# 05-Front_Panel_SFP_1.net
KiCad netlist of a schematic drawn in Altium Designer
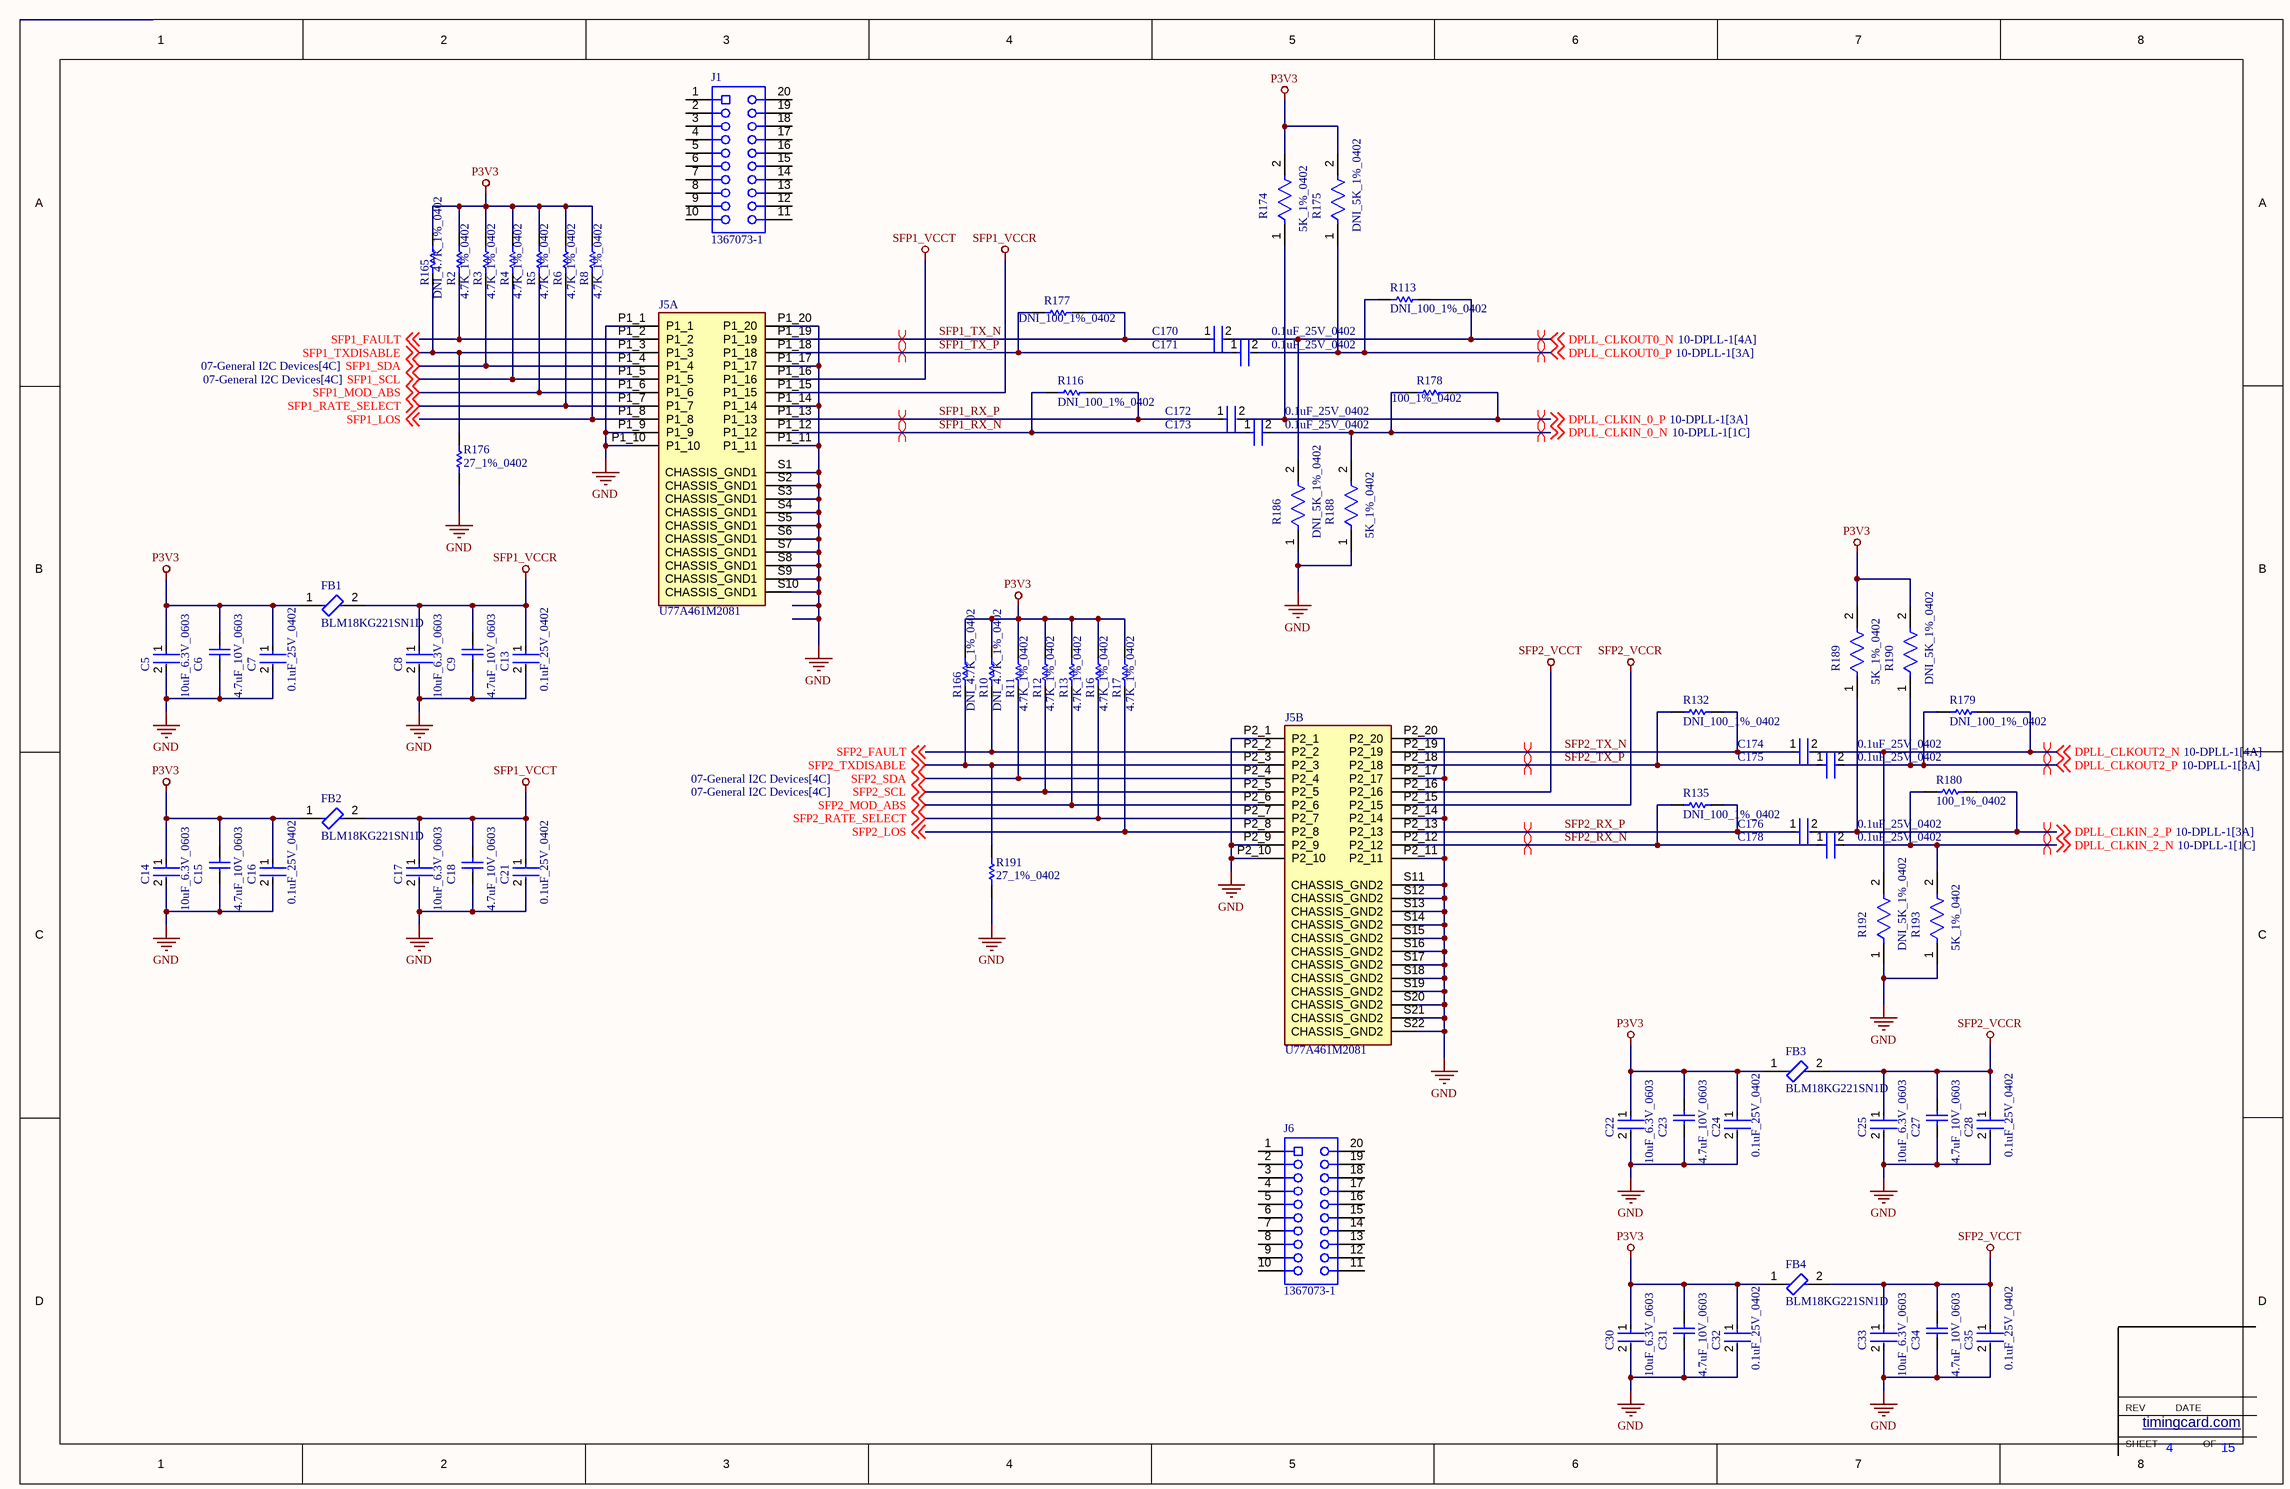
[diagram p0: 05-Front Panel SFP_1.SchDoc]

(export (version "E")
  (design (tool "Eeschema 10.0.6"))
  (components
    (comp (ref "C5")
      (value "10uF_6.3V_0603")
      (footprint "FP-C0603C106M9PACTU-MFG")
      (description "CAP CER 10UF 6.3V X5R 0603")
      (fields
        (field (name "MANUFACTURER PART NUMBER") "C0603C106M9PACTU")
        (field (name "MANUFACTURER") "Kemet")
      )
      (libsource (lib "Altium Content Vault") (part "b4654b650e69147ec39a6b967a45e02"))
    )
    (comp (ref "C6")
      (value "4.7uF_10V_0603")
      (footprint "CAPC1608X87X35NL15T15")
      (fields (field (name "PART NUMBER") "C0603C475K8PACTU") (field (name "MANUFACTURER") "Kemet"))
      (libsource (lib "Altium Content Vault") (part "CAP"))
    )
    (comp (ref "C7")
      (value "0.1uF_25V_0402")
      (footprint "FP-0402-L_1_0_1-W_0_5_0_1-IPC_C")
      (description "General Purpose Ceramic Capacitor, 0402, 100nF, 10%, X7R, 15%, 25V")
      (fields (field (name "VOLTAGE") "25V") (field (name "TOLERANCE") "10%"))
      (libsource (lib "Altium Content Vault") (part "b4654b650e69147ec39a6b967a45e02"))
    )
    (comp (ref "C8")
      (value "10uF_6.3V_0603")
      (footprint "FP-C0603C106M9PACTU-MFG")
      (description "CAP CER 10UF 6.3V X5R 0603")
      (fields
        (field (name "MANUFACTURER PART NUMBER") "C0603C106M9PACTU")
        (field (name "MANUFACTURER") "Kemet")
      )
      (libsource (lib "Altium Content Vault") (part "b4654b650e69147ec39a6b967a45e02"))
    )
    (comp (ref "C9")
      (value "4.7uF_10V_0603")
      (footprint "CAPC1608X87X35NL15T15")
      (fields (field (name "PART NUMBER") "C0603C475K8PACTU") (field (name "MANUFACTURER") "Kemet"))
      (libsource (lib "Altium Content Vault") (part "CAP"))
    )
    (comp (ref "C13")
      (value "0.1uF_25V_0402")
      (footprint "FP-0402-L_1_0_1-W_0_5_0_1-IPC_C")
      (description "General Purpose Ceramic Capacitor, 0402, 100nF, 10%, X7R, 15%, 25V")
      (fields (field (name "VOLTAGE") "25V") (field (name "TOLERANCE") "10%"))
      (libsource (lib "Altium Content Vault") (part "b4654b650e69147ec39a6b967a45e02"))
    )
    (comp (ref "C14")
      (value "10uF_6.3V_0603")
      (footprint "FP-C0603C106M9PACTU-MFG")
      (description "CAP CER 10UF 6.3V X5R 0603")
      (fields
        (field (name "MANUFACTURER PART NUMBER") "C0603C106M9PACTU")
        (field (name "MANUFACTURER") "Kemet")
      )
      (libsource (lib "Altium Content Vault") (part "b4654b650e69147ec39a6b967a45e02"))
    )
    (comp (ref "C15")
      (value "4.7uF_10V_0603")
      (footprint "CAPC1608X87X35NL15T15")
      (fields (field (name "PART NUMBER") "C0603C475K8PACTU") (field (name "MANUFACTURER") "Kemet"))
      (libsource (lib "Altium Content Vault") (part "CAP"))
    )
    (comp (ref "C16")
      (value "0.1uF_25V_0402")
      (footprint "FP-0402-L_1_0_1-W_0_5_0_1-IPC_C")
      (description "General Purpose Ceramic Capacitor, 0402, 100nF, 10%, X7R, 15%, 25V")
      (fields (field (name "VOLTAGE") "25V") (field (name "TOLERANCE") "10%"))
      (libsource (lib "Altium Content Vault") (part "b4654b650e69147ec39a6b967a45e02"))
    )
    (comp (ref "C17")
      (value "10uF_6.3V_0603")
      (footprint "FP-C0603C106M9PACTU-MFG")
      (description "CAP CER 10UF 6.3V X5R 0603")
      (fields
        (field (name "MANUFACTURER PART NUMBER") "C0603C106M9PACTU")
        (field (name "MANUFACTURER") "Kemet")
      )
      (libsource (lib "Altium Content Vault") (part "b4654b650e69147ec39a6b967a45e02"))
    )
    (comp (ref "C18")
      (value "4.7uF_10V_0603")
      (footprint "CAPC1608X87X35NL15T15")
      (fields (field (name "PART NUMBER") "C0603C475K8PACTU") (field (name "MANUFACTURER") "Kemet"))
      (libsource (lib "Altium Content Vault") (part "CAP"))
    )
    (comp (ref "C21")
      (value "0.1uF_25V_0402")
      (footprint "FP-0402-L_1_0_1-W_0_5_0_1-IPC_C")
      (description "General Purpose Ceramic Capacitor, 0402, 100nF, 10%, X7R, 15%, 25V")
      (fields (field (name "VOLTAGE") "25V") (field (name "TOLERANCE") "10%"))
      (libsource (lib "Altium Content Vault") (part "b4654b650e69147ec39a6b967a45e02"))
    )
    (comp (ref "C22")
      (value "10uF_6.3V_0603")
      (footprint "FP-C0603C106M9PACTU-MFG")
      (description "CAP CER 10UF 6.3V X5R 0603")
      (fields
        (field (name "MANUFACTURER PART NUMBER") "C0603C106M9PACTU")
        (field (name "MANUFACTURER") "Kemet")
      )
      (libsource (lib "Altium Content Vault") (part "b4654b650e69147ec39a6b967a45e02"))
    )
    (comp (ref "C23")
      (value "4.7uF_10V_0603")
      (footprint "CAPC1608X87X35NL15T15")
      (fields (field (name "PART NUMBER") "C0603C475K8PACTU") (field (name "MANUFACTURER") "Kemet"))
      (libsource (lib "Altium Content Vault") (part "CAP"))
    )
    (comp (ref "C24")
      (value "0.1uF_25V_0402")
      (footprint "FP-0402-L_1_0_1-W_0_5_0_1-IPC_C")
      (description "General Purpose Ceramic Capacitor, 0402, 100nF, 10%, X7R, 15%, 25V")
      (fields (field (name "VOLTAGE") "25V") (field (name "TOLERANCE") "10%"))
      (libsource (lib "Altium Content Vault") (part "b4654b650e69147ec39a6b967a45e02"))
    )
    (comp (ref "C25")
      (value "10uF_6.3V_0603")
      (footprint "FP-C0603C106M9PACTU-MFG")
      (description "CAP CER 10UF 6.3V X5R 0603")
      (fields
        (field (name "MANUFACTURER PART NUMBER") "C0603C106M9PACTU")
        (field (name "MANUFACTURER") "Kemet")
      )
      (libsource (lib "Altium Content Vault") (part "b4654b650e69147ec39a6b967a45e02"))
    )
    (comp (ref "C27")
      (value "4.7uF_10V_0603")
      (footprint "CAPC1608X87X35NL15T15")
      (fields (field (name "PART NUMBER") "C0603C475K8PACTU") (field (name "MANUFACTURER") "Kemet"))
      (libsource (lib "Altium Content Vault") (part "CAP"))
    )
    (comp (ref "C28")
      (value "0.1uF_25V_0402")
      (footprint "FP-0402-L_1_0_1-W_0_5_0_1-IPC_C")
      (description "General Purpose Ceramic Capacitor, 0402, 100nF, 10%, X7R, 15%, 25V")
      (fields (field (name "VOLTAGE") "25V") (field (name "TOLERANCE") "10%"))
      (libsource (lib "Altium Content Vault") (part "b4654b650e69147ec39a6b967a45e02"))
    )
    (comp (ref "C30")
      (value "10uF_6.3V_0603")
      (footprint "FP-C0603C106M9PACTU-MFG")
      (description "CAP CER 10UF 6.3V X5R 0603")
      (fields
        (field (name "MANUFACTURER PART NUMBER") "C0603C106M9PACTU")
        (field (name "MANUFACTURER") "Kemet")
      )
      (libsource (lib "Altium Content Vault") (part "b4654b650e69147ec39a6b967a45e02"))
    )
    (comp (ref "C31")
      (value "4.7uF_10V_0603")
      (footprint "CAPC1608X87X35NL15T15")
      (fields (field (name "PART NUMBER") "C0603C475K8PACTU") (field (name "MANUFACTURER") "Kemet"))
      (libsource (lib "Altium Content Vault") (part "CAP"))
    )
    (comp (ref "C32")
      (value "0.1uF_25V_0402")
      (footprint "FP-0402-L_1_0_1-W_0_5_0_1-IPC_C")
      (description "General Purpose Ceramic Capacitor, 0402, 100nF, 10%, X7R, 15%, 25V")
      (fields (field (name "VOLTAGE") "25V") (field (name "TOLERANCE") "10%"))
      (libsource (lib "Altium Content Vault") (part "b4654b650e69147ec39a6b967a45e02"))
    )
    (comp (ref "C33")
      (value "10uF_6.3V_0603")
      (footprint "FP-C0603C106M9PACTU-MFG")
      (description "CAP CER 10UF 6.3V X5R 0603")
      (fields
        (field (name "MANUFACTURER PART NUMBER") "C0603C106M9PACTU")
        (field (name "MANUFACTURER") "Kemet")
      )
      (libsource (lib "Altium Content Vault") (part "b4654b650e69147ec39a6b967a45e02"))
    )
    (comp (ref "C34")
      (value "4.7uF_10V_0603")
      (footprint "CAPC1608X87X35NL15T15")
      (fields (field (name "PART NUMBER") "C0603C475K8PACTU") (field (name "MANUFACTURER") "Kemet"))
      (libsource (lib "Altium Content Vault") (part "CAP"))
    )
    (comp (ref "C35")
      (value "0.1uF_25V_0402")
      (footprint "FP-0402-L_1_0_1-W_0_5_0_1-IPC_C")
      (description "General Purpose Ceramic Capacitor, 0402, 100nF, 10%, X7R, 15%, 25V")
      (fields (field (name "VOLTAGE") "25V") (field (name "TOLERANCE") "10%"))
      (libsource (lib "Altium Content Vault") (part "b4654b650e69147ec39a6b967a45e02"))
    )
    (comp (ref "C170")
      (value "0.1uF_25V_0402")
      (footprint "FP-0402-L_1_0_1-W_0_5_0_1-IPC_C")
      (description "General Purpose Ceramic Capacitor, 0402, 100nF, 10%, X7R, 15%, 25V")
      (fields (field (name "VOLTAGE") "25V") (field (name "TOLERANCE") "10%"))
      (libsource (lib "Altium Content Vault") (part "b4654b650e69147ec39a6b967a45e02"))
    )
    (comp (ref "C171")
      (value "0.1uF_25V_0402")
      (footprint "FP-0402-L_1_0_1-W_0_5_0_1-IPC_C")
      (description "General Purpose Ceramic Capacitor, 0402, 100nF, 10%, X7R, 15%, 25V")
      (fields (field (name "VOLTAGE") "25V") (field (name "TOLERANCE") "10%"))
      (libsource (lib "Altium Content Vault") (part "b4654b650e69147ec39a6b967a45e02"))
    )
    (comp (ref "C172")
      (value "0.1uF_25V_0402")
      (footprint "FP-0402-L_1_0_1-W_0_5_0_1-IPC_C")
      (description "General Purpose Ceramic Capacitor, 0402, 100nF, 10%, X7R, 15%, 25V")
      (fields (field (name "VOLTAGE") "25V") (field (name "TOLERANCE") "10%"))
      (libsource (lib "Altium Content Vault") (part "b4654b650e69147ec39a6b967a45e02"))
    )
    (comp (ref "C173")
      (value "0.1uF_25V_0402")
      (footprint "FP-0402-L_1_0_1-W_0_5_0_1-IPC_C")
      (description "General Purpose Ceramic Capacitor, 0402, 100nF, 10%, X7R, 15%, 25V")
      (fields (field (name "VOLTAGE") "25V") (field (name "TOLERANCE") "10%"))
      (libsource (lib "Altium Content Vault") (part "b4654b650e69147ec39a6b967a45e02"))
    )
    (comp (ref "C174")
      (value "0.1uF_25V_0402")
      (footprint "FP-0402-L_1_0_1-W_0_5_0_1-IPC_C")
      (description "General Purpose Ceramic Capacitor, 0402, 100nF, 10%, X7R, 15%, 25V")
      (fields (field (name "VOLTAGE") "25V") (field (name "TOLERANCE") "10%"))
      (libsource (lib "Altium Content Vault") (part "b4654b650e69147ec39a6b967a45e02"))
    )
    (comp (ref "C175")
      (value "0.1uF_25V_0402")
      (footprint "FP-0402-L_1_0_1-W_0_5_0_1-IPC_C")
      (description "General Purpose Ceramic Capacitor, 0402, 100nF, 10%, X7R, 15%, 25V")
      (fields (field (name "VOLTAGE") "25V") (field (name "TOLERANCE") "10%"))
      (libsource (lib "Altium Content Vault") (part "b4654b650e69147ec39a6b967a45e02"))
    )
    (comp (ref "C176")
      (value "0.1uF_25V_0402")
      (footprint "FP-0402-L_1_0_1-W_0_5_0_1-IPC_C")
      (description "General Purpose Ceramic Capacitor, 0402, 100nF, 10%, X7R, 15%, 25V")
      (fields (field (name "VOLTAGE") "25V") (field (name "TOLERANCE") "10%"))
      (libsource (lib "Altium Content Vault") (part "b4654b650e69147ec39a6b967a45e02"))
    )
    (comp (ref "C178")
      (value "0.1uF_25V_0402")
      (footprint "FP-0402-L_1_0_1-W_0_5_0_1-IPC_C")
      (description "General Purpose Ceramic Capacitor, 0402, 100nF, 10%, X7R, 15%, 25V")
      (fields (field (name "VOLTAGE") "25V") (field (name "TOLERANCE") "10%"))
      (libsource (lib "Altium Content Vault") (part "b4654b650e69147ec39a6b967a45e02"))
    )
    (comp (ref "FB1")
      (value "BLM18KG221SN1D")
      (footprint "FP-BLM18-0_15-t0_8-IPC_B")
      (description "Chip Ferrite Bead, 0603, 220Ω @ 100MHz, 0.05Ω, 25%, 2.2A")
      (fields (field (name "TOLERANCE") "25%"))
      (libsource (lib "Altium Content Vault") (part "5f30dd21d616792df468990f7003faa"))
    )
    (comp (ref "FB2")
      (value "BLM18KG221SN1D")
      (footprint "FP-BLM18-0_15-t0_8-IPC_B")
      (description "Chip Ferrite Bead, 0603, 220Ω @ 100MHz, 0.05Ω, 25%, 2.2A")
      (fields (field (name "TOLERANCE") "25%"))
      (libsource (lib "Altium Content Vault") (part "5f30dd21d616792df468990f7003faa"))
    )
    (comp (ref "FB3")
      (value "BLM18KG221SN1D")
      (footprint "FP-BLM18-0_15-t0_8-IPC_B")
      (description "Chip Ferrite Bead, 0603, 220Ω @ 100MHz, 0.05Ω, 25%, 2.2A")
      (fields (field (name "TOLERANCE") "25%"))
      (libsource (lib "Altium Content Vault") (part "5f30dd21d616792df468990f7003faa"))
    )
    (comp (ref "FB4")
      (value "BLM18KG221SN1D")
      (footprint "FP-BLM18-0_15-t0_8-IPC_B")
      (description "Chip Ferrite Bead, 0603, 220Ω @ 100MHz, 0.05Ω, 25%, 2.2A")
      (fields (field (name "TOLERANCE") "25%"))
      (libsource (lib "Altium Content Vault") (part "5f30dd21d616792df468990f7003faa"))
    )
    (comp (ref "J1")
      (value "1367073-1")
      (footprint "TECO-1367073-1_V")
      (fields (field (name "MANUFACTURER") "TE Connectivity"))
      (libsource (lib "Altium Content Vault") (part "CN-2P-F-R20_B"))
    )
    (comp (ref "J5")
      (value "U77A461M2081")
      (footprint "AMPHENOL_U77A461M2081")
      (fields (field (name "MF") "AMPHENOL ICC / FCI"))
      (libsource (lib "U77A461M2081") (part "U77A461M2081"))
    )
    (comp (ref "J6")
      (value "1367073-1")
      (footprint "TECO-1367073-1_V")
      (fields (field (name "MANUFACTURER") "TE Connectivity"))
      (libsource (lib "Altium Content Vault") (part "CN-2P-F-R20_B"))
    )
    (comp (ref "R2")
      (value "4.7K_1%_0402")
      (footprint "RESC1005X40X25NL10T10")
      (fields (field (name "MANUFACTURER") "Bourns") (field (name "PART NUMBER") "CR0402-FX-4701GLF"))
      (libsource (lib "Altium Content Vault") (part "RES"))
    )
    (comp (ref "R3")
      (value "4.7K_1%_0402")
      (footprint "RESC1005X40X25NL10T10")
      (fields (field (name "MANUFACTURER") "Bourns") (field (name "PART NUMBER") "CR0402-FX-4701GLF"))
      (libsource (lib "Altium Content Vault") (part "RES"))
    )
    (comp (ref "R4")
      (value "4.7K_1%_0402")
      (footprint "RESC1005X40X25NL10T10")
      (fields (field (name "MANUFACTURER") "Bourns") (field (name "PART NUMBER") "CR0402-FX-4701GLF"))
      (libsource (lib "Altium Content Vault") (part "RES"))
    )
    (comp (ref "R5")
      (value "4.7K_1%_0402")
      (footprint "RESC1005X40X25NL10T10")
      (fields (field (name "MANUFACTURER") "Bourns") (field (name "PART NUMBER") "CR0402-FX-4701GLF"))
      (libsource (lib "Altium Content Vault") (part "RES"))
    )
    (comp (ref "R6")
      (value "4.7K_1%_0402")
      (footprint "RESC1005X40X25NL10T10")
      (fields (field (name "MANUFACTURER") "Bourns") (field (name "PART NUMBER") "CR0402-FX-4701GLF"))
      (libsource (lib "Altium Content Vault") (part "RES"))
    )
    (comp (ref "R8")
      (value "4.7K_1%_0402")
      (footprint "RESC1005X40X25NL10T10")
      (fields (field (name "MANUFACTURER") "Bourns") (field (name "PART NUMBER") "CR0402-FX-4701GLF"))
      (libsource (lib "Altium Content Vault") (part "RES"))
    )
    (comp (ref "R10")
      (value "DNI_4.7K_1%_0402")
      (footprint "RESC1005X40X25NL10T10")
      (fields (field (name "MANUFACTURER") "Bourns") (field (name "PART NUMBER") "CR0402-FX-4701GLF"))
      (libsource (lib "Altium Content Vault") (part "RES"))
    )
    (comp (ref "R11")
      (value "4.7K_1%_0402")
      (footprint "RESC1005X40X25NL10T10")
      (fields (field (name "MANUFACTURER") "Bourns") (field (name "PART NUMBER") "CR0402-FX-4701GLF"))
      (libsource (lib "Altium Content Vault") (part "RES"))
    )
    (comp (ref "R12")
      (value "4.7K_1%_0402")
      (footprint "RESC1005X40X25NL10T10")
      (fields (field (name "MANUFACTURER") "Bourns") (field (name "PART NUMBER") "CR0402-FX-4701GLF"))
      (libsource (lib "Altium Content Vault") (part "RES"))
    )
    (comp (ref "R13")
      (value "4.7K_1%_0402")
      (footprint "RESC1005X40X25NL10T10")
      (fields (field (name "MANUFACTURER") "Bourns") (field (name "PART NUMBER") "CR0402-FX-4701GLF"))
      (libsource (lib "Altium Content Vault") (part "RES"))
    )
    (comp (ref "R16")
      (value "4.7K_1%_0402")
      (footprint "RESC1005X40X25NL10T10")
      (fields (field (name "MANUFACTURER") "Bourns") (field (name "PART NUMBER") "CR0402-FX-4701GLF"))
      (libsource (lib "Altium Content Vault") (part "RES"))
    )
    (comp (ref "R17")
      (value "4.7K_1%_0402")
      (footprint "RESC1005X40X25NL10T10")
      (fields (field (name "MANUFACTURER") "Bourns") (field (name "PART NUMBER") "CR0402-FX-4701GLF"))
      (libsource (lib "Altium Content Vault") (part "RES"))
    )
    (comp (ref "R113")
      (value "DNI_100_1%_0402")
      (footprint "RESC1005X40X25NL05T10")
      (fields (field (name "MANUFACTURER") "Yageo") (field (name "PART NUMBER") "RC0402FR-13100RL"))
      (libsource (lib "Altium Content Vault") (part "RES"))
    )
    (comp (ref "R116")
      (value "DNI_100_1%_0402")
      (footprint "RESC1005X40X25NL05T10")
      (fields (field (name "MANUFACTURER") "Yageo") (field (name "PART NUMBER") "RC0402FR-13100RL"))
      (libsource (lib "Altium Content Vault") (part "RES"))
    )
    (comp (ref "R132")
      (value "DNI_100_1%_0402")
      (footprint "RESC1005X40X25NL05T10")
      (fields (field (name "MANUFACTURER") "Yageo") (field (name "PART NUMBER") "RC0402FR-13100RL"))
      (libsource (lib "Altium Content Vault") (part "RES"))
    )
    (comp (ref "R135")
      (value "DNI_100_1%_0402")
      (footprint "RESC1005X40X25NL05T10")
      (fields (field (name "MANUFACTURER") "Yageo") (field (name "PART NUMBER") "RC0402FR-13100RL"))
      (libsource (lib "Altium Content Vault") (part "RES"))
    )
    (comp (ref "R165")
      (value "DNI_4.7K_1%_0402")
      (footprint "RESC1005X40X25NL10T10")
      (fields (field (name "MANUFACTURER") "Bourns") (field (name "PART NUMBER") "CR0402-FX-4701GLF"))
      (libsource (lib "Altium Content Vault") (part "RES"))
    )
    (comp (ref "R166")
      (value "DNI_4.7K_1%_0402")
      (footprint "RESC1005X40X25NL10T10")
      (fields (field (name "MANUFACTURER") "Bourns") (field (name "PART NUMBER") "CR0402-FX-4701GLF"))
      (libsource (lib "Altium Content Vault") (part "RES"))
    )
    (comp (ref "R174")
      (value "5K_1%_0402")
      (footprint "FP-RC0402-MFG")
      (description "RES SMD 5K OHM 1% 1/16W 0402")
      (fields (field (name "MANUFACTURER") "Yageo") (field (name "TOLERANCE") "1%"))
      (libsource (lib "Altium Content Vault") (part "1029c3af85768c4190bb7ad29bc67b5"))
    )
    (comp (ref "R175")
      (value "DNI_5K_1%_0402")
      (footprint "FP-RC0402-MFG")
      (description "RES SMD 5K OHM 1% 1/16W 0402")
      (fields (field (name "MANUFACTURER") "Yageo") (field (name "TOLERANCE") "1%"))
      (libsource (lib "Altium Content Vault") (part "1029c3af85768c4190bb7ad29bc67b5"))
    )
    (comp (ref "R176")
      (value "27_1%_0402")
      (footprint "RESC1005X40X25NL05T05")
      (fields (field (name "PART NUMBER") "CRCW040227R0FKED") (field (name "MANUFACTURER") "Vishay Dale"))
      (libsource (lib "Altium Content Vault") (part "RES"))
    )
    (comp (ref "R177")
      (value "DNI_100_1%_0402")
      (footprint "RESC1005X40X25NL05T10")
      (fields (field (name "MANUFACTURER") "Yageo") (field (name "PART NUMBER") "RC0402FR-13100RL"))
      (libsource (lib "Altium Content Vault") (part "RES"))
    )
    (comp (ref "R178")
      (value "100_1%_0402")
      (footprint "RESC1005X40X25NL05T10")
      (fields (field (name "MANUFACTURER") "Yageo") (field (name "PART NUMBER") "RC0402FR-13100RL"))
      (libsource (lib "Altium Content Vault") (part "RES"))
    )
    (comp (ref "R179")
      (value "DNI_100_1%_0402")
      (footprint "RESC1005X40X25NL05T10")
      (fields (field (name "MANUFACTURER") "Yageo") (field (name "PART NUMBER") "RC0402FR-13100RL"))
      (libsource (lib "Altium Content Vault") (part "RES"))
    )
    (comp (ref "R180")
      (value "100_1%_0402")
      (footprint "RESC1005X40X25NL05T10")
      (fields (field (name "MANUFACTURER") "Yageo") (field (name "PART NUMBER") "RC0402FR-13100RL"))
      (libsource (lib "Altium Content Vault") (part "RES"))
    )
    (comp (ref "R186")
      (value "DNI_5K_1%_0402")
      (footprint "FP-RC0402-MFG")
      (description "RES SMD 5K OHM 1% 1/16W 0402")
      (fields (field (name "MANUFACTURER") "Yageo") (field (name "TOLERANCE") "1%"))
      (libsource (lib "Altium Content Vault") (part "1029c3af85768c4190bb7ad29bc67b5"))
    )
    (comp (ref "R188")
      (value "5K_1%_0402")
      (footprint "FP-RC0402-MFG")
      (description "RES SMD 5K OHM 1% 1/16W 0402")
      (fields (field (name "MANUFACTURER") "Yageo") (field (name "TOLERANCE") "1%"))
      (libsource (lib "Altium Content Vault") (part "1029c3af85768c4190bb7ad29bc67b5"))
    )
    (comp (ref "R189")
      (value "5K_1%_0402")
      (footprint "FP-RC0402-MFG")
      (description "RES SMD 5K OHM 1% 1/16W 0402")
      (fields (field (name "MANUFACTURER") "Yageo") (field (name "TOLERANCE") "1%"))
      (libsource (lib "Altium Content Vault") (part "1029c3af85768c4190bb7ad29bc67b5"))
    )
    (comp (ref "R190")
      (value "DNI_5K_1%_0402")
      (footprint "FP-RC0402-MFG")
      (description "RES SMD 5K OHM 1% 1/16W 0402")
      (fields (field (name "MANUFACTURER") "Yageo") (field (name "TOLERANCE") "1%"))
      (libsource (lib "Altium Content Vault") (part "1029c3af85768c4190bb7ad29bc67b5"))
    )
    (comp (ref "R191")
      (value "27_1%_0402")
      (footprint "RESC1005X40X25NL05T05")
      (fields (field (name "PART NUMBER") "CRCW040227R0FKED") (field (name "MANUFACTURER") "Vishay Dale"))
      (libsource (lib "Altium Content Vault") (part "RES"))
    )
    (comp (ref "R192")
      (value "DNI_5K_1%_0402")
      (footprint "FP-RC0402-MFG")
      (description "RES SMD 5K OHM 1% 1/16W 0402")
      (fields (field (name "MANUFACTURER") "Yageo") (field (name "TOLERANCE") "1%"))
      (libsource (lib "Altium Content Vault") (part "1029c3af85768c4190bb7ad29bc67b5"))
    )
    (comp (ref "R193")
      (value "5K_1%_0402")
      (footprint "FP-RC0402-MFG")
      (description "RES SMD 5K OHM 1% 1/16W 0402")
      (fields (field (name "MANUFACTURER") "Yageo") (field (name "TOLERANCE") "1%"))
      (libsource (lib "Altium Content Vault") (part "1029c3af85768c4190bb7ad29bc67b5"))
    )
  )
  (nets
    (net (code "1") (name "/SFP1_RX_N") (class "Default")
      (node (ref "C173") (pin "1") (pinfunction "1_1") (pintype "passive"))
      (node (ref "J5") (pin "P1_12") (pinfunction "P1_12_P1_12") (pintype "passive"))
      (node (ref "R116") (pin "1") (pinfunction "1_1") (pintype "passive"))
    )
    (net (code "2") (name "/SFP1_RX_P") (class "Default")
      (node (ref "C172") (pin "1") (pinfunction "1_1") (pintype "passive"))
      (node (ref "J5") (pin "P1_13") (pinfunction "P1_13_P1_13") (pintype "passive"))
      (node (ref "R116") (pin "2") (pinfunction "2_2") (pintype "passive"))
    )
    (net (code "3") (name "/SFP1_TX_N") (class "Default")
      (node (ref "C170") (pin "1") (pinfunction "1_1") (pintype "passive"))
      (node (ref "J5") (pin "P1_19") (pinfunction "P1_19_P1_19") (pintype "passive"))
      (node (ref "R177") (pin "2") (pinfunction "2_2") (pintype "passive"))
    )
    (net (code "4") (name "/SFP1_TX_P") (class "Default")
      (node (ref "C171") (pin "1") (pinfunction "1_1") (pintype "passive"))
      (node (ref "J5") (pin "P1_18") (pinfunction "P1_18_P1_18") (pintype "passive"))
      (node (ref "R177") (pin "1") (pinfunction "1_1") (pintype "passive"))
    )
    (net (code "5") (name "/SFP2_RX_N") (class "Default")
      (node (ref "C178") (pin "1") (pinfunction "1_1") (pintype "passive"))
      (node (ref "J5") (pin "P2_12") (pinfunction "P2_12_P2_12") (pintype "passive"))
      (node (ref "R135") (pin "1") (pinfunction "1_1") (pintype "passive"))
    )
    (net (code "6") (name "/SFP2_RX_P") (class "Default")
      (node (ref "C176") (pin "1") (pinfunction "1_1") (pintype "passive"))
      (node (ref "J5") (pin "P2_13") (pinfunction "P2_13_P2_13") (pintype "passive"))
      (node (ref "R135") (pin "2") (pinfunction "2_2") (pintype "passive"))
    )
    (net (code "7") (name "/SFP2_TX_N") (class "Default")
      (node (ref "C174") (pin "1") (pinfunction "1_1") (pintype "passive"))
      (node (ref "J5") (pin "P2_19") (pinfunction "P2_19_P2_19") (pintype "passive"))
      (node (ref "R132") (pin "2") (pinfunction "2_2") (pintype "passive"))
    )
    (net (code "8") (name "/SFP2_TX_P") (class "Default")
      (node (ref "C175") (pin "1") (pinfunction "1_1") (pintype "passive"))
      (node (ref "J5") (pin "P2_18") (pinfunction "P2_18_P2_18") (pintype "passive"))
      (node (ref "R132") (pin "1") (pinfunction "1_1") (pintype "passive"))
    )
    (net (code "9") (name "DPLL_CLKIN_0_N") (class "Default")
      (node (ref "C173") (pin "2") (pinfunction "2_2") (pintype "passive"))
      (node (ref "R178") (pin "1") (pinfunction "1_1") (pintype "passive"))
      (node (ref "R188") (pin "2") (pinfunction "2_2") (pintype "passive"))
    )
    (net (code "10") (name "DPLL_CLKIN_0_P") (class "Default")
      (node (ref "C172") (pin "2") (pinfunction "2_2") (pintype "passive"))
      (node (ref "R174") (pin "1") (pinfunction "1_1") (pintype "passive"))
      (node (ref "R178") (pin "2") (pinfunction "2_2") (pintype "passive"))
    )
    (net (code "11") (name "DPLL_CLKIN_2_N") (class "Default")
      (node (ref "C178") (pin "2") (pinfunction "2_2") (pintype "passive"))
      (node (ref "R180") (pin "1") (pinfunction "1_1") (pintype "passive"))
      (node (ref "R193") (pin "2") (pinfunction "2_2") (pintype "passive"))
    )
    (net (code "12") (name "DPLL_CLKIN_2_P") (class "Default")
      (node (ref "C176") (pin "2") (pinfunction "2_2") (pintype "passive"))
      (node (ref "R180") (pin "2") (pinfunction "2_2") (pintype "passive"))
      (node (ref "R189") (pin "1") (pinfunction "1_1") (pintype "passive"))
    )
    (net (code "13") (name "DPLL_CLKOUT0_N") (class "Default")
      (node (ref "C170") (pin "2") (pinfunction "2_2") (pintype "passive"))
      (node (ref "R113") (pin "2") (pinfunction "2_2") (pintype "passive"))
      (node (ref "R186") (pin "2") (pinfunction "2_2") (pintype "passive"))
    )
    (net (code "14") (name "DPLL_CLKOUT0_P") (class "Default")
      (node (ref "C171") (pin "2") (pinfunction "2_2") (pintype "passive"))
      (node (ref "R113") (pin "1") (pinfunction "1_1") (pintype "passive"))
      (node (ref "R175") (pin "1") (pinfunction "1_1") (pintype "passive"))
    )
    (net (code "15") (name "DPLL_CLKOUT2_N") (class "Default")
      (node (ref "C174") (pin "2") (pinfunction "2_2") (pintype "passive"))
      (node (ref "R179") (pin "2") (pinfunction "2_2") (pintype "passive"))
      (node (ref "R192") (pin "2") (pinfunction "2_2") (pintype "passive"))
    )
    (net (code "16") (name "DPLL_CLKOUT2_P") (class "Default")
      (node (ref "C175") (pin "2") (pinfunction "2_2") (pintype "passive"))
      (node (ref "R179") (pin "1") (pinfunction "1_1") (pintype "passive"))
      (node (ref "R190") (pin "1") (pinfunction "1_1") (pintype "passive"))
    )
    (net (code "17") (name "GND") (class "Default")
      (node (ref "C13") (pin "2") (pinfunction "2_2") (pintype "passive"))
      (node (ref "C14") (pin "2") (pinfunction "2_2") (pintype "passive"))
      (node (ref "C15") (pin "1") (pinfunction "1_1") (pintype "passive"))
      (node (ref "C16") (pin "2") (pinfunction "2_2") (pintype "passive"))
      (node (ref "C17") (pin "2") (pinfunction "2_2") (pintype "passive"))
      (node (ref "C18") (pin "1") (pinfunction "1_1") (pintype "passive"))
      (node (ref "C21") (pin "2") (pinfunction "2_2") (pintype "passive"))
      (node (ref "C22") (pin "2") (pinfunction "2_2") (pintype "passive"))
      (node (ref "C23") (pin "1") (pinfunction "1_1") (pintype "passive"))
      (node (ref "C24") (pin "2") (pinfunction "2_2") (pintype "passive"))
      (node (ref "C25") (pin "2") (pinfunction "2_2") (pintype "passive"))
      (node (ref "C27") (pin "1") (pinfunction "1_1") (pintype "passive"))
      (node (ref "C28") (pin "2") (pinfunction "2_2") (pintype "passive"))
      (node (ref "C30") (pin "2") (pinfunction "2_2") (pintype "passive"))
      (node (ref "C31") (pin "1") (pinfunction "1_1") (pintype "passive"))
      (node (ref "C32") (pin "2") (pinfunction "2_2") (pintype "passive"))
      (node (ref "C33") (pin "2") (pinfunction "2_2") (pintype "passive"))
      (node (ref "C34") (pin "1") (pinfunction "1_1") (pintype "passive"))
      (node (ref "C35") (pin "2") (pinfunction "2_2") (pintype "passive"))
      (node (ref "C5") (pin "2") (pinfunction "2_2") (pintype "passive"))
      (node (ref "C6") (pin "1") (pinfunction "1_1") (pintype "passive"))
      (node (ref "C7") (pin "2") (pinfunction "2_2") (pintype "passive"))
      (node (ref "C8") (pin "2") (pinfunction "2_2") (pintype "passive"))
      (node (ref "C9") (pin "1") (pinfunction "1_1") (pintype "passive"))
      (node (ref "J5") (pin "P1_1") (pinfunction "P1_1_P1_1") (pintype "passive"))
      (node (ref "J5") (pin "P1_10") (pinfunction "P1_10_P1_10") (pintype "passive"))
      (node (ref "J5") (pin "P1_11") (pinfunction "P1_11_P1_11") (pintype "passive"))
      (node (ref "J5") (pin "P1_14") (pinfunction "P1_14_P1_14") (pintype "passive"))
      (node (ref "J5") (pin "P1_17") (pinfunction "P1_17_P1_17") (pintype "passive"))
      (node (ref "J5") (pin "P1_20") (pinfunction "P1_20_P1_20") (pintype "passive"))
      (node (ref "J5") (pin "P1_9") (pinfunction "P1_9_P1_9") (pintype "passive"))
      (node (ref "J5") (pin "P2_1") (pinfunction "P2_1_P2_1") (pintype "passive"))
      (node (ref "J5") (pin "P2_10") (pinfunction "P2_10_P2_10") (pintype "passive"))
      (node (ref "J5") (pin "P2_11") (pinfunction "P2_11_P2_11") (pintype "passive"))
      (node (ref "J5") (pin "P2_14") (pinfunction "P2_14_P2_14") (pintype "passive"))
      (node (ref "J5") (pin "P2_17") (pinfunction "P2_17_P2_17") (pintype "passive"))
      (node (ref "J5") (pin "P2_20") (pinfunction "P2_20_P2_20") (pintype "passive"))
      (node (ref "J5") (pin "P2_9") (pinfunction "P2_9_P2_9") (pintype "passive"))
      (node (ref "J5") (pin "S1") (pinfunction "CHASSIS_GND1_S1") (pintype "power_in"))
      (node (ref "J5") (pin "S10") (pinfunction "CHASSIS_GND1_S10") (pintype "power_in"))
      (node (ref "J5") (pin "S11") (pinfunction "CHASSIS_GND2_S11") (pintype "passive"))
      (node (ref "J5") (pin "S12") (pinfunction "CHASSIS_GND2_S12") (pintype "passive"))
      (node (ref "J5") (pin "S13") (pinfunction "CHASSIS_GND2_S13") (pintype "passive"))
      (node (ref "J5") (pin "S14") (pinfunction "CHASSIS_GND2_S14") (pintype "passive"))
      (node (ref "J5") (pin "S15") (pinfunction "CHASSIS_GND2_S15") (pintype "passive"))
      (node (ref "J5") (pin "S16") (pinfunction "CHASSIS_GND2_S16") (pintype "passive"))
      (node (ref "J5") (pin "S17") (pinfunction "CHASSIS_GND2_S17") (pintype "passive"))
      (node (ref "J5") (pin "S18") (pinfunction "CHASSIS_GND2_S18") (pintype "passive"))
      (node (ref "J5") (pin "S19") (pinfunction "CHASSIS_GND2_S19") (pintype "passive"))
      (node (ref "J5") (pin "S2") (pinfunction "CHASSIS_GND1_S2") (pintype "power_in"))
      (node (ref "J5") (pin "S20") (pinfunction "CHASSIS_GND2_S20") (pintype "passive"))
      (node (ref "J5") (pin "S21") (pinfunction "CHASSIS_GND2_S21") (pintype "passive"))
      (node (ref "J5") (pin "S22") (pinfunction "CHASSIS_GND2_S22") (pintype "passive"))
      (node (ref "J5") (pin "S3") (pinfunction "CHASSIS_GND1_S3") (pintype "power_in"))
      (node (ref "J5") (pin "S4") (pinfunction "CHASSIS_GND1_S4") (pintype "power_in"))
      (node (ref "J5") (pin "S5") (pinfunction "CHASSIS_GND1_S5") (pintype "power_in"))
      (node (ref "J5") (pin "S6") (pinfunction "CHASSIS_GND1_S6") (pintype "power_in"))
      (node (ref "J5") (pin "S7") (pinfunction "CHASSIS_GND1_S7") (pintype "power_in"))
      (node (ref "J5") (pin "S8") (pinfunction "CHASSIS_GND1_S8") (pintype "power_in"))
      (node (ref "J5") (pin "S9") (pinfunction "CHASSIS_GND1_S9") (pintype "power_in"))
      (node (ref "R176") (pin "1") (pinfunction "1_1") (pintype "passive"))
      (node (ref "R186") (pin "1") (pinfunction "1_1") (pintype "passive"))
      (node (ref "R188") (pin "1") (pinfunction "1_1") (pintype "passive"))
      (node (ref "R191") (pin "1") (pinfunction "1_1") (pintype "passive"))
      (node (ref "R192") (pin "1") (pinfunction "1_1") (pintype "passive"))
      (node (ref "R193") (pin "1") (pinfunction "1_1") (pintype "passive"))
    )
    (net (code "18") (name "P3V3") (class "Default")
      (node (ref "C14") (pin "1") (pinfunction "1_1") (pintype "passive"))
      (node (ref "C15") (pin "2") (pinfunction "2_2") (pintype "passive"))
      (node (ref "C16") (pin "1") (pinfunction "1_1") (pintype "passive"))
      (node (ref "C22") (pin "1") (pinfunction "1_1") (pintype "passive"))
      (node (ref "C23") (pin "2") (pinfunction "2_2") (pintype "passive"))
      (node (ref "C24") (pin "1") (pinfunction "1_1") (pintype "passive"))
      (node (ref "C30") (pin "1") (pinfunction "1_1") (pintype "passive"))
      (node (ref "C31") (pin "2") (pinfunction "2_2") (pintype "passive"))
      (node (ref "C32") (pin "1") (pinfunction "1_1") (pintype "passive"))
      (node (ref "C5") (pin "1") (pinfunction "1_1") (pintype "passive"))
      (node (ref "C6") (pin "2") (pinfunction "2_2") (pintype "passive"))
      (node (ref "C7") (pin "1") (pinfunction "1_1") (pintype "passive"))
      (node (ref "FB1") (pin "1") (pinfunction "1_1") (pintype "passive"))
      (node (ref "FB2") (pin "1") (pinfunction "1_1") (pintype "passive"))
      (node (ref "FB3") (pin "1") (pinfunction "1_1") (pintype "passive"))
      (node (ref "FB4") (pin "1") (pinfunction "1_1") (pintype "passive"))
      (node (ref "R10") (pin "1") (pinfunction "1_1") (pintype "passive"))
      (node (ref "R11") (pin "1") (pinfunction "1_1") (pintype "passive"))
      (node (ref "R12") (pin "1") (pinfunction "1_1") (pintype "passive"))
      (node (ref "R13") (pin "1") (pinfunction "1_1") (pintype "passive"))
      (node (ref "R16") (pin "1") (pinfunction "1_1") (pintype "passive"))
      (node (ref "R165") (pin "1") (pinfunction "1_1") (pintype "passive"))
      (node (ref "R166") (pin "1") (pinfunction "1_1") (pintype "passive"))
      (node (ref "R17") (pin "1") (pinfunction "1_1") (pintype "passive"))
      (node (ref "R174") (pin "2") (pinfunction "2_2") (pintype "passive"))
      (node (ref "R175") (pin "2") (pinfunction "2_2") (pintype "passive"))
      (node (ref "R189") (pin "2") (pinfunction "2_2") (pintype "passive"))
      (node (ref "R190") (pin "2") (pinfunction "2_2") (pintype "passive"))
      (node (ref "R2") (pin "1") (pinfunction "1_1") (pintype "passive"))
      (node (ref "R3") (pin "1") (pinfunction "1_1") (pintype "passive"))
      (node (ref "R4") (pin "1") (pinfunction "1_1") (pintype "passive"))
      (node (ref "R5") (pin "1") (pinfunction "1_1") (pintype "passive"))
      (node (ref "R6") (pin "1") (pinfunction "1_1") (pintype "passive"))
      (node (ref "R8") (pin "1") (pinfunction "1_1") (pintype "passive"))
    )
    (net (code "19") (name "SFP1_FAULT") (class "Default")
      (node (ref "J5") (pin "P1_2") (pinfunction "P1_2_P1_2") (pintype "passive"))
      (node (ref "R2") (pin "2") (pinfunction "2_2") (pintype "passive"))
    )
    (net (code "20") (name "SFP1_LOS") (class "Default")
      (node (ref "J5") (pin "P1_8") (pinfunction "P1_8_P1_8") (pintype "passive"))
      (node (ref "R8") (pin "2") (pinfunction "2_2") (pintype "passive"))
    )
    (net (code "21") (name "SFP1_MOD_ABS") (class "Default")
      (node (ref "J5") (pin "P1_6") (pinfunction "P1_6_P1_6") (pintype "passive"))
      (node (ref "R5") (pin "2") (pinfunction "2_2") (pintype "passive"))
    )
    (net (code "22") (name "SFP1_RATE_SELECT") (class "Default")
      (node (ref "J5") (pin "P1_7") (pinfunction "P1_7_P1_7") (pintype "passive"))
      (node (ref "R6") (pin "2") (pinfunction "2_2") (pintype "passive"))
    )
    (net (code "23") (name "SFP1_SCL") (class "Default")
      (node (ref "J5") (pin "P1_5") (pinfunction "P1_5_P1_5") (pintype "passive"))
      (node (ref "R4") (pin "2") (pinfunction "2_2") (pintype "passive"))
    )
    (net (code "24") (name "SFP1_SDA") (class "Default")
      (node (ref "J5") (pin "P1_4") (pinfunction "P1_4_P1_4") (pintype "passive"))
      (node (ref "R3") (pin "2") (pinfunction "2_2") (pintype "passive"))
    )
    (net (code "25") (name "SFP1_TXDISABLE") (class "Default")
      (node (ref "J5") (pin "P1_3") (pinfunction "P1_3_P1_3") (pintype "passive"))
      (node (ref "R165") (pin "2") (pinfunction "2_2") (pintype "passive"))
      (node (ref "R176") (pin "2") (pinfunction "2_2") (pintype "passive"))
    )
    (net (code "26") (name "SFP1_VCCR") (class "Default")
      (node (ref "C13") (pin "1") (pinfunction "1_1") (pintype "passive"))
      (node (ref "C8") (pin "1") (pinfunction "1_1") (pintype "passive"))
      (node (ref "C9") (pin "2") (pinfunction "2_2") (pintype "passive"))
      (node (ref "FB1") (pin "2") (pinfunction "2_2") (pintype "passive"))
      (node (ref "J5") (pin "P1_15") (pinfunction "P1_15_P1_15") (pintype "passive"))
    )
    (net (code "27") (name "SFP1_VCCT") (class "Default")
      (node (ref "C17") (pin "1") (pinfunction "1_1") (pintype "passive"))
      (node (ref "C18") (pin "2") (pinfunction "2_2") (pintype "passive"))
      (node (ref "C21") (pin "1") (pinfunction "1_1") (pintype "passive"))
      (node (ref "FB2") (pin "2") (pinfunction "2_2") (pintype "passive"))
      (node (ref "J5") (pin "P1_16") (pinfunction "P1_16_P1_16") (pintype "passive"))
    )
    (net (code "28") (name "SFP2_FAULT") (class "Default")
      (node (ref "J5") (pin "P2_2") (pinfunction "P2_2_P2_2") (pintype "passive"))
      (node (ref "R10") (pin "2") (pinfunction "2_2") (pintype "passive"))
    )
    (net (code "29") (name "SFP2_LOS") (class "Default")
      (node (ref "J5") (pin "P2_8") (pinfunction "P2_8_P2_8") (pintype "passive"))
      (node (ref "R17") (pin "2") (pinfunction "2_2") (pintype "passive"))
    )
    (net (code "30") (name "SFP2_MOD_ABS") (class "Default")
      (node (ref "J5") (pin "P2_6") (pinfunction "P2_6_P2_6") (pintype "passive"))
      (node (ref "R13") (pin "2") (pinfunction "2_2") (pintype "passive"))
    )
    (net (code "31") (name "SFP2_RATE_SELECT") (class "Default")
      (node (ref "J5") (pin "P2_7") (pinfunction "P2_7_P2_7") (pintype "passive"))
      (node (ref "R16") (pin "2") (pinfunction "2_2") (pintype "passive"))
    )
    (net (code "32") (name "SFP2_SCL") (class "Default")
      (node (ref "J5") (pin "P2_5") (pinfunction "P2_5_P2_5") (pintype "passive"))
      (node (ref "R12") (pin "2") (pinfunction "2_2") (pintype "passive"))
    )
    (net (code "33") (name "SFP2_SDA") (class "Default")
      (node (ref "J5") (pin "P2_4") (pinfunction "P2_4_P2_4") (pintype "passive"))
      (node (ref "R11") (pin "2") (pinfunction "2_2") (pintype "passive"))
    )
    (net (code "34") (name "SFP2_TXDISABLE") (class "Default")
      (node (ref "J5") (pin "P2_3") (pinfunction "P2_3_P2_3") (pintype "passive"))
      (node (ref "R166") (pin "2") (pinfunction "2_2") (pintype "passive"))
      (node (ref "R191") (pin "2") (pinfunction "2_2") (pintype "passive"))
    )
    (net (code "35") (name "SFP2_VCCR") (class "Default")
      (node (ref "C25") (pin "1") (pinfunction "1_1") (pintype "passive"))
      (node (ref "C27") (pin "2") (pinfunction "2_2") (pintype "passive"))
      (node (ref "C28") (pin "1") (pinfunction "1_1") (pintype "passive"))
      (node (ref "FB3") (pin "2") (pinfunction "2_2") (pintype "passive"))
      (node (ref "J5") (pin "P2_15") (pinfunction "P2_15_P2_15") (pintype "passive"))
    )
    (net (code "36") (name "SFP2_VCCT") (class "Default")
      (node (ref "C33") (pin "1") (pinfunction "1_1") (pintype "passive"))
      (node (ref "C34") (pin "2") (pinfunction "2_2") (pintype "passive"))
      (node (ref "C35") (pin "1") (pinfunction "1_1") (pintype "passive"))
      (node (ref "FB4") (pin "2") (pinfunction "2_2") (pintype "passive"))
      (node (ref "J5") (pin "P2_16") (pinfunction "P2_16_P2_16") (pintype "passive"))
    )
    (net (code "37") (name "unconnected-(J1-Pad1)") (class "Default")
      (node (ref "J1") (pin "1") (pinfunction "1_1") (pintype "passive"))
    )
    (net (code "38") (name "unconnected-(J1-Pad2)") (class "Default")
      (node (ref "J1") (pin "2") (pinfunction "2_2") (pintype "passive"))
    )
    (net (code "39") (name "unconnected-(J1-Pad3)") (class "Default")
      (node (ref "J1") (pin "3") (pinfunction "3_3") (pintype "passive"))
    )
    (net (code "40") (name "unconnected-(J1-Pad4)") (class "Default")
      (node (ref "J1") (pin "4") (pinfunction "4_4") (pintype "passive"))
    )
    (net (code "41") (name "unconnected-(J1-Pad5)") (class "Default")
      (node (ref "J1") (pin "5") (pinfunction "5_5") (pintype "passive"))
    )
    (net (code "42") (name "unconnected-(J1-Pad6)") (class "Default")
      (node (ref "J1") (pin "6") (pinfunction "6_6") (pintype "passive"))
    )
    (net (code "43") (name "unconnected-(J1-Pad7)") (class "Default")
      (node (ref "J1") (pin "7") (pinfunction "7_7") (pintype "passive"))
    )
    (net (code "44") (name "unconnected-(J1-Pad8)") (class "Default")
      (node (ref "J1") (pin "8") (pinfunction "8_8") (pintype "passive"))
    )
    (net (code "45") (name "unconnected-(J1-Pad9)") (class "Default")
      (node (ref "J1") (pin "9") (pinfunction "9_9") (pintype "passive"))
    )
    (net (code "46") (name "unconnected-(J1-Pad10)") (class "Default")
      (node (ref "J1") (pin "10") (pinfunction "10_10") (pintype "passive"))
    )
    (net (code "47") (name "unconnected-(J1-Pad11)") (class "Default")
      (node (ref "J1") (pin "11") (pinfunction "11_11") (pintype "passive"))
    )
    (net (code "48") (name "unconnected-(J1-Pad12)") (class "Default")
      (node (ref "J1") (pin "12") (pinfunction "12_12") (pintype "passive"))
    )
    (net (code "49") (name "unconnected-(J1-Pad13)") (class "Default")
      (node (ref "J1") (pin "13") (pinfunction "13_13") (pintype "passive"))
    )
    (net (code "50") (name "unconnected-(J1-Pad14)") (class "Default")
      (node (ref "J1") (pin "14") (pinfunction "14_14") (pintype "passive"))
    )
    (net (code "51") (name "unconnected-(J1-Pad15)") (class "Default")
      (node (ref "J1") (pin "15") (pinfunction "15_15") (pintype "passive"))
    )
    (net (code "52") (name "unconnected-(J1-Pad16)") (class "Default")
      (node (ref "J1") (pin "16") (pinfunction "16_16") (pintype "passive"))
    )
    (net (code "53") (name "unconnected-(J1-Pad17)") (class "Default")
      (node (ref "J1") (pin "17") (pinfunction "17_17") (pintype "passive"))
    )
    (net (code "54") (name "unconnected-(J1-Pad18)") (class "Default")
      (node (ref "J1") (pin "18") (pinfunction "18_18") (pintype "passive"))
    )
    (net (code "55") (name "unconnected-(J1-Pad19)") (class "Default")
      (node (ref "J1") (pin "19") (pinfunction "19_19") (pintype "passive"))
    )
    (net (code "56") (name "unconnected-(J1-Pad20)") (class "Default")
      (node (ref "J1") (pin "20") (pinfunction "20_20") (pintype "passive"))
    )
    (net (code "57") (name "unconnected-(J6-Pad1)") (class "Default")
      (node (ref "J6") (pin "1") (pinfunction "1_1") (pintype "passive"))
    )
    (net (code "58") (name "unconnected-(J6-Pad2)") (class "Default")
      (node (ref "J6") (pin "2") (pinfunction "2_2") (pintype "passive"))
    )
    (net (code "59") (name "unconnected-(J6-Pad3)") (class "Default")
      (node (ref "J6") (pin "3") (pinfunction "3_3") (pintype "passive"))
    )
    (net (code "60") (name "unconnected-(J6-Pad4)") (class "Default")
      (node (ref "J6") (pin "4") (pinfunction "4_4") (pintype "passive"))
    )
    (net (code "61") (name "unconnected-(J6-Pad5)") (class "Default")
      (node (ref "J6") (pin "5") (pinfunction "5_5") (pintype "passive"))
    )
    (net (code "62") (name "unconnected-(J6-Pad6)") (class "Default")
      (node (ref "J6") (pin "6") (pinfunction "6_6") (pintype "passive"))
    )
    (net (code "63") (name "unconnected-(J6-Pad7)") (class "Default")
      (node (ref "J6") (pin "7") (pinfunction "7_7") (pintype "passive"))
    )
    (net (code "64") (name "unconnected-(J6-Pad8)") (class "Default")
      (node (ref "J6") (pin "8") (pinfunction "8_8") (pintype "passive"))
    )
    (net (code "65") (name "unconnected-(J6-Pad9)") (class "Default")
      (node (ref "J6") (pin "9") (pinfunction "9_9") (pintype "passive"))
    )
    (net (code "66") (name "unconnected-(J6-Pad10)") (class "Default")
      (node (ref "J6") (pin "10") (pinfunction "10_10") (pintype "passive"))
    )
    (net (code "67") (name "unconnected-(J6-Pad11)") (class "Default")
      (node (ref "J6") (pin "11") (pinfunction "11_11") (pintype "passive"))
    )
    (net (code "68") (name "unconnected-(J6-Pad12)") (class "Default")
      (node (ref "J6") (pin "12") (pinfunction "12_12") (pintype "passive"))
    )
    (net (code "69") (name "unconnected-(J6-Pad13)") (class "Default")
      (node (ref "J6") (pin "13") (pinfunction "13_13") (pintype "passive"))
    )
    (net (code "70") (name "unconnected-(J6-Pad14)") (class "Default")
      (node (ref "J6") (pin "14") (pinfunction "14_14") (pintype "passive"))
    )
    (net (code "71") (name "unconnected-(J6-Pad15)") (class "Default")
      (node (ref "J6") (pin "15") (pinfunction "15_15") (pintype "passive"))
    )
    (net (code "72") (name "unconnected-(J6-Pad16)") (class "Default")
      (node (ref "J6") (pin "16") (pinfunction "16_16") (pintype "passive"))
    )
    (net (code "73") (name "unconnected-(J6-Pad17)") (class "Default")
      (node (ref "J6") (pin "17") (pinfunction "17_17") (pintype "passive"))
    )
    (net (code "74") (name "unconnected-(J6-Pad18)") (class "Default")
      (node (ref "J6") (pin "18") (pinfunction "18_18") (pintype "passive"))
    )
    (net (code "75") (name "unconnected-(J6-Pad19)") (class "Default")
      (node (ref "J6") (pin "19") (pinfunction "19_19") (pintype "passive"))
    )
    (net (code "76") (name "unconnected-(J6-Pad20)") (class "Default")
      (node (ref "J6") (pin "20") (pinfunction "20_20") (pintype "passive"))
    )
  )
)
